# m4_Dev_Board.net
KiCad netlist of a schematic drawn in EAGLE
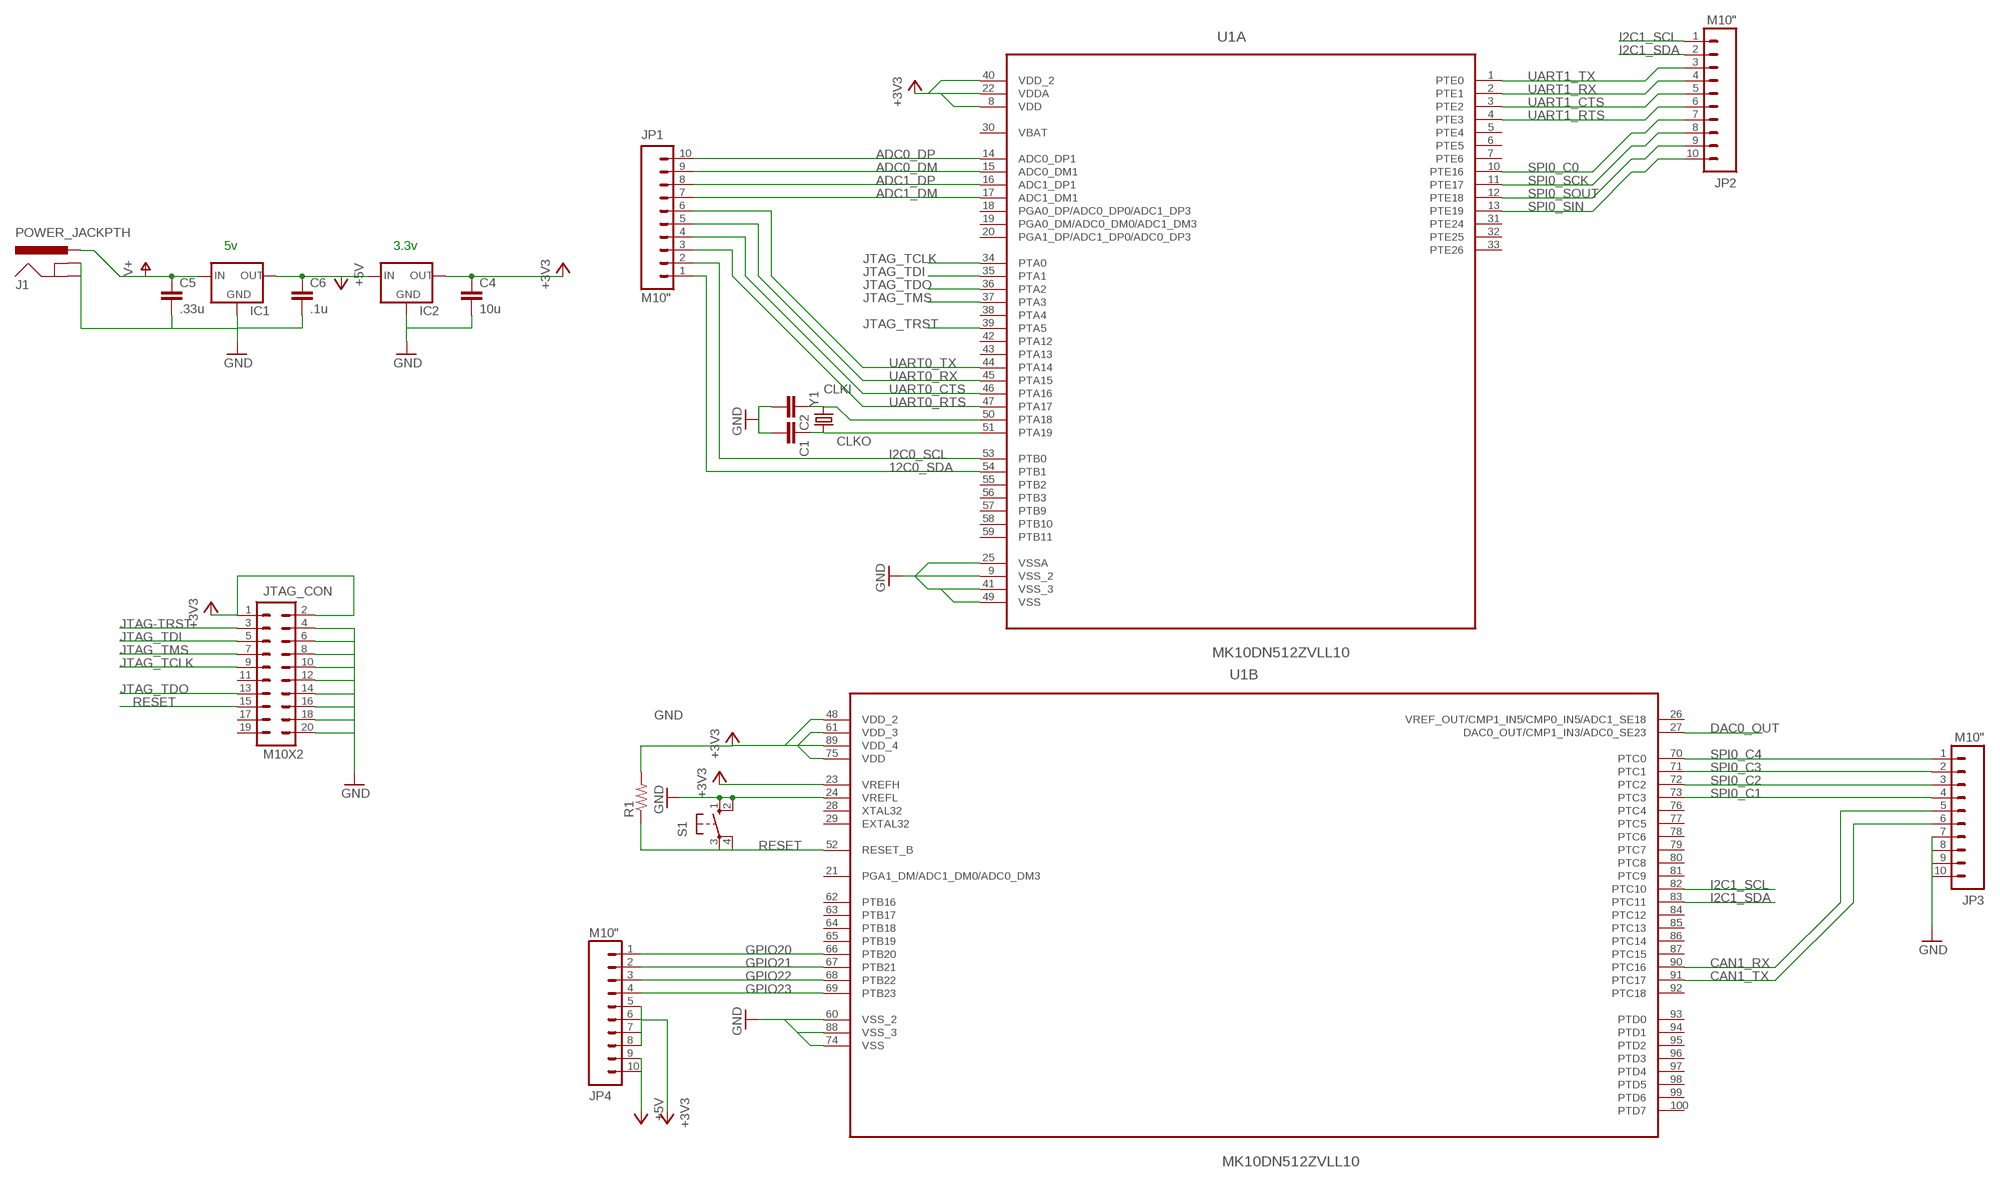
[diagram p0: schematic, sheet 1]

(export (version "E")
  (design (tool "Eeschema 10.0.6"))
  (components
    (comp (ref "C1")
      (value "CAPPTH1")
      (footprint "eagle-import:CAP-PTH-5MM")
      (libsource (lib "eagle-import") (part "CAPPTH1"))
    )
    (comp (ref "C2")
      (value "CAPPTH1")
      (footprint "eagle-import:CAP-PTH-5MM")
      (libsource (lib "eagle-import") (part "CAPPTH1"))
    )
    (comp (ref "C4")
      (value "10u")
      (footprint "eagle-import:CAP-PTH-5MM")
      (libsource (lib "eagle-import") (part "CAPPTH1"))
    )
    (comp (ref "C5")
      (value ".33u")
      (footprint "eagle-import:CAP-PTH-5MM")
      (libsource (lib "eagle-import") (part "CAPPTH1"))
    )
    (comp (ref "C6")
      (value ".1u")
      (footprint "eagle-import:CAP-PTH-5MM")
      (libsource (lib "eagle-import") (part "CAPPTH1"))
    )
    (comp (ref "IC1")
      (value "V_REG_78XXSINK")
      (footprint "eagle-import:TO220-IGO")
      (libsource (lib "eagle-import") (part "V_REG_78XXSINK"))
    )
    (comp (ref "IC2")
      (value "V_REG_78XXSINK")
      (footprint "eagle-import:TO220-IGO")
      (libsource (lib "eagle-import") (part "V_REG_78XXSINK"))
    )
    (comp (ref "J1")
      (value "POWER_JACKPTH")
      (footprint "eagle-import:POWER_JACK_PTH")
      (libsource (lib "eagle-import") (part "POWER_JACKPTH"))
    )
    (comp (ref "JP1")
      (value "M10\"")
      (footprint "eagle-import:1X10")
      (libsource (lib "eagle-import") (part "M10{dblquote}"))
    )
    (comp (ref "JP2")
      (value "M10\"")
      (footprint "eagle-import:1X10")
      (libsource (lib "eagle-import") (part "M10{dblquote}"))
    )
    (comp (ref "JP3")
      (value "M10\"")
      (footprint "eagle-import:1X10")
      (libsource (lib "eagle-import") (part "M10{dblquote}"))
    )
    (comp (ref "JP4")
      (value "M10\"")
      (footprint "eagle-import:1X10")
      (libsource (lib "eagle-import") (part "M10{dblquote}"))
    )
    (comp (ref "JTAG_CON")
      (value "M10X2")
      (footprint "eagle-import:2X10")
      (libsource (lib "eagle-import") (part "M10X2"))
    )
    (comp (ref "R1")
      (value "RESISTORPTH-1/4W")
      (footprint "eagle-import:AXIAL-0.4")
      (libsource (lib "eagle-import") (part "RESISTORPTH-1/4W"))
    )
    (comp (ref "S1")
      (value "10-XX")
      (footprint "eagle-import:B3F-10XX")
      (fields (field (name "MPN") "B3F-1000"))
      (libsource (lib "eagle-import") (part "10-XX"))
    )
    (comp (ref "U1")
      (value "MK10DN512ZVLL10")
      (footprint "eagle-import:QFP50P1600X1600X170-100N")
      (libsource (lib "eagle-import") (part "MK10DN512ZVLL10"))
    )
    (comp (ref "Y1")
      (value "CRYSTALHC49US")
      (footprint "eagle-import:HC49US")
      (libsource (lib "eagle-import") (part "CRYSTALHC49US"))
    )
  )
  (nets
    (net (code "1") (name "+3V3") (class "Default")
      (node (ref "C4") (pin "1") (pinfunction "1_1") (pintype "passive"))
      (node (ref "IC2") (pin "OUT") (pinfunction "OUT_OUT") (pintype "output"))
      (node (ref "JP4") (pin "5") (pinfunction "5_5") (pintype "passive"))
      (node (ref "JP4") (pin "6") (pinfunction "6_6") (pintype "passive"))
      (node (ref "JP4") (pin "7") (pinfunction "7_7") (pintype "passive"))
      (node (ref "JP4") (pin "8") (pinfunction "8_8") (pintype "passive"))
      (node (ref "JTAG_CON") (pin "1") (pinfunction "1_1") (pintype "passive"))
      (node (ref "JTAG_CON") (pin "2") (pinfunction "2_2") (pintype "passive"))
      (node (ref "R1") (pin "P$2") (pinfunction "2_P$2") (pintype "passive"))
      (node (ref "U1") (pin "22") (pinfunction "VDDA_22") (pintype "power_in"))
      (node (ref "U1") (pin "23") (pinfunction "VREFH_23") (pintype "passive"))
      (node (ref "U1") (pin "40") (pinfunction "VDD_2_40") (pintype "power_in"))
      (node (ref "U1") (pin "48") (pinfunction "VDD_2_48") (pintype "power_in"))
      (node (ref "U1") (pin "61") (pinfunction "VDD_3_61") (pintype "power_in"))
      (node (ref "U1") (pin "75") (pinfunction "VDD_75") (pintype "power_in"))
      (node (ref "U1") (pin "8") (pinfunction "VDD_8") (pintype "power_in"))
      (node (ref "U1") (pin "89") (pinfunction "VDD_4_89") (pintype "power_in"))
    )
    (net (code "2") (name "+5V") (class "Default")
      (node (ref "C6") (pin "1") (pinfunction "1_1") (pintype "passive"))
      (node (ref "IC1") (pin "OUT") (pinfunction "OUT_OUT") (pintype "output"))
      (node (ref "IC2") (pin "IN") (pinfunction "IN_IN") (pintype "input"))
      (node (ref "JP4") (pin "10") (pinfunction "10_10") (pintype "passive"))
      (node (ref "JP4") (pin "9") (pinfunction "9_9") (pintype "passive"))
    )
    (net (code "3") (name "/12C0_SDA") (class "Default")
      (node (ref "JP1") (pin "1") (pinfunction "1_1") (pintype "passive"))
      (node (ref "U1") (pin "54") (pinfunction "PTB1_54") (pintype "bidirectional"))
    )
    (net (code "4") (name "/ADC0_DM") (class "Default")
      (node (ref "JP1") (pin "9") (pinfunction "9_9") (pintype "passive"))
      (node (ref "U1") (pin "15") (pinfunction "ADC0_DM1_15") (pintype "passive"))
    )
    (net (code "5") (name "/ADC0_DP") (class "Default")
      (node (ref "JP1") (pin "10") (pinfunction "10_10") (pintype "passive"))
      (node (ref "U1") (pin "14") (pinfunction "ADC0_DP1_14") (pintype "passive"))
    )
    (net (code "6") (name "/ADC1_DM") (class "Default")
      (node (ref "JP1") (pin "7") (pinfunction "7_7") (pintype "passive"))
      (node (ref "U1") (pin "17") (pinfunction "ADC1_DM1_17") (pintype "passive"))
    )
    (net (code "7") (name "/ADC1_DP") (class "Default")
      (node (ref "JP1") (pin "8") (pinfunction "8_8") (pintype "passive"))
      (node (ref "U1") (pin "16") (pinfunction "ADC1_DP1_16") (pintype "passive"))
    )
    (net (code "8") (name "/CAN1_RX") (class "Default")
      (node (ref "JP3") (pin "5") (pinfunction "5_5") (pintype "passive"))
      (node (ref "U1") (pin "90") (pinfunction "PTC16_90") (pintype "bidirectional"))
    )
    (net (code "9") (name "/CAN1_TX") (class "Default")
      (node (ref "JP3") (pin "6") (pinfunction "6_6") (pintype "passive"))
      (node (ref "U1") (pin "91") (pinfunction "PTC17_91") (pintype "bidirectional"))
    )
    (net (code "10") (name "/CLKI") (class "Default")
      (node (ref "C2") (pin "1") (pinfunction "1_1") (pintype "passive"))
      (node (ref "U1") (pin "50") (pinfunction "PTA18_50") (pintype "bidirectional"))
      (node (ref "Y1") (pin "2") (pinfunction "2_2") (pintype "passive"))
    )
    (net (code "11") (name "/CLKO") (class "Default")
      (node (ref "C1") (pin "1") (pinfunction "1_1") (pintype "passive"))
      (node (ref "U1") (pin "51") (pinfunction "PTA19_51") (pintype "bidirectional"))
      (node (ref "Y1") (pin "1") (pinfunction "1_1") (pintype "passive"))
    )
    (net (code "12") (name "/DAC0_OUT") (class "Default")
      (node (ref "U1") (pin "27") (pinfunction "DAC0_OUT/CMP1_IN3/ADC0_SE23_27") (pintype "passive"))
    )
    (net (code "13") (name "/GPIO20") (class "Default")
      (node (ref "JP4") (pin "1") (pinfunction "1_1") (pintype "passive"))
      (node (ref "U1") (pin "66") (pinfunction "PTB20_66") (pintype "bidirectional"))
    )
    (net (code "14") (name "/GPIO21") (class "Default")
      (node (ref "JP4") (pin "2") (pinfunction "2_2") (pintype "passive"))
      (node (ref "U1") (pin "67") (pinfunction "PTB21_67") (pintype "bidirectional"))
    )
    (net (code "15") (name "/GPIO22") (class "Default")
      (node (ref "JP4") (pin "3") (pinfunction "3_3") (pintype "passive"))
      (node (ref "U1") (pin "68") (pinfunction "PTB22_68") (pintype "bidirectional"))
    )
    (net (code "16") (name "/GPIO23") (class "Default")
      (node (ref "JP4") (pin "4") (pinfunction "4_4") (pintype "passive"))
      (node (ref "U1") (pin "69") (pinfunction "PTB23_69") (pintype "bidirectional"))
    )
    (net (code "17") (name "/I2C0_SCL") (class "Default")
      (node (ref "JP1") (pin "2") (pinfunction "2_2") (pintype "passive"))
      (node (ref "U1") (pin "53") (pinfunction "PTB0_53") (pintype "bidirectional"))
    )
    (net (code "18") (name "/I2C1_SCL") (class "Default")
      (node (ref "JP2") (pin "1") (pinfunction "1_1") (pintype "passive"))
      (node (ref "U1") (pin "82") (pinfunction "PTC10_82") (pintype "bidirectional"))
    )
    (net (code "19") (name "/I2C1_SDA") (class "Default")
      (node (ref "JP2") (pin "2") (pinfunction "2_2") (pintype "passive"))
      (node (ref "U1") (pin "83") (pinfunction "PTC11_83") (pintype "bidirectional"))
    )
    (net (code "20") (name "/JTAG-TRST") (class "Default")
      (node (ref "JTAG_CON") (pin "3") (pinfunction "3_3") (pintype "passive"))
    )
    (net (code "21") (name "/JTAG_TCLK") (class "Default")
      (node (ref "JTAG_CON") (pin "9") (pinfunction "9_9") (pintype "passive"))
      (node (ref "U1") (pin "34") (pinfunction "PTA0_34") (pintype "bidirectional"))
    )
    (net (code "22") (name "/JTAG_TDI") (class "Default")
      (node (ref "JTAG_CON") (pin "5") (pinfunction "5_5") (pintype "passive"))
      (node (ref "U1") (pin "35") (pinfunction "PTA1_35") (pintype "bidirectional"))
    )
    (net (code "23") (name "/JTAG_TDO") (class "Default")
      (node (ref "JTAG_CON") (pin "13") (pinfunction "13_13") (pintype "passive"))
      (node (ref "U1") (pin "36") (pinfunction "PTA2_36") (pintype "bidirectional"))
    )
    (net (code "24") (name "/JTAG_TMS") (class "Default")
      (node (ref "JTAG_CON") (pin "7") (pinfunction "7_7") (pintype "passive"))
      (node (ref "U1") (pin "37") (pinfunction "PTA3_37") (pintype "bidirectional"))
    )
    (net (code "25") (name "/JTAG_TRST") (class "Default")
      (node (ref "U1") (pin "39") (pinfunction "PTA5_39") (pintype "bidirectional"))
    )
    (net (code "26") (name "/RESET") (class "Default")
      (node (ref "JTAG_CON") (pin "15") (pinfunction "15_15") (pintype "passive"))
      (node (ref "R1") (pin "P$1") (pinfunction "1_P$1") (pintype "passive"))
      (node (ref "S1") (pin "3") (pinfunction "P_3") (pintype "passive"))
      (node (ref "S1") (pin "4") (pinfunction "P1_4") (pintype "passive"))
      (node (ref "U1") (pin "52") (pinfunction "RESET_B_52") (pintype "passive"))
    )
    (net (code "27") (name "/SPI0_C0") (class "Default")
      (node (ref "JP2") (pin "7") (pinfunction "7_7") (pintype "passive"))
      (node (ref "U1") (pin "10") (pinfunction "PTE16_10") (pintype "bidirectional"))
    )
    (net (code "28") (name "/SPI0_C1") (class "Default")
      (node (ref "JP3") (pin "4") (pinfunction "4_4") (pintype "passive"))
      (node (ref "U1") (pin "73") (pinfunction "PTC3_73") (pintype "bidirectional"))
    )
    (net (code "29") (name "/SPI0_C2") (class "Default")
      (node (ref "JP3") (pin "3") (pinfunction "3_3") (pintype "passive"))
      (node (ref "U1") (pin "72") (pinfunction "PTC2_72") (pintype "bidirectional"))
    )
    (net (code "30") (name "/SPI0_C3") (class "Default")
      (node (ref "JP3") (pin "2") (pinfunction "2_2") (pintype "passive"))
      (node (ref "U1") (pin "71") (pinfunction "PTC1_71") (pintype "bidirectional"))
    )
    (net (code "31") (name "/SPI0_C4") (class "Default")
      (node (ref "JP3") (pin "1") (pinfunction "1_1") (pintype "passive"))
      (node (ref "U1") (pin "70") (pinfunction "PTC0_70") (pintype "bidirectional"))
    )
    (net (code "32") (name "/SPI0_SCK") (class "Default")
      (node (ref "JP2") (pin "8") (pinfunction "8_8") (pintype "passive"))
      (node (ref "U1") (pin "11") (pinfunction "PTE17_11") (pintype "bidirectional"))
    )
    (net (code "33") (name "/SPI0_SIN") (class "Default")
      (node (ref "JP2") (pin "10") (pinfunction "10_10") (pintype "passive"))
      (node (ref "U1") (pin "13") (pinfunction "PTE19_13") (pintype "bidirectional"))
    )
    (net (code "34") (name "/SPI0_SOUT") (class "Default")
      (node (ref "JP2") (pin "9") (pinfunction "9_9") (pintype "passive"))
      (node (ref "U1") (pin "12") (pinfunction "PTE18_12") (pintype "bidirectional"))
    )
    (net (code "35") (name "/UART0_CTS") (class "Default")
      (node (ref "JP1") (pin "4") (pinfunction "4_4") (pintype "passive"))
      (node (ref "U1") (pin "46") (pinfunction "PTA16_46") (pintype "bidirectional"))
    )
    (net (code "36") (name "/UART0_RTS") (class "Default")
      (node (ref "JP1") (pin "3") (pinfunction "3_3") (pintype "passive"))
      (node (ref "U1") (pin "47") (pinfunction "PTA17_47") (pintype "bidirectional"))
    )
    (net (code "37") (name "/UART0_RX") (class "Default")
      (node (ref "JP1") (pin "5") (pinfunction "5_5") (pintype "passive"))
      (node (ref "U1") (pin "45") (pinfunction "PTA15_45") (pintype "bidirectional"))
    )
    (net (code "38") (name "/UART0_TX") (class "Default")
      (node (ref "JP1") (pin "6") (pinfunction "6_6") (pintype "passive"))
      (node (ref "U1") (pin "44") (pinfunction "PTA14_44") (pintype "bidirectional"))
    )
    (net (code "39") (name "/UART1_CTS") (class "Default")
      (node (ref "JP2") (pin "5") (pinfunction "5_5") (pintype "passive"))
      (node (ref "U1") (pin "3") (pinfunction "PTE2_3") (pintype "bidirectional"))
    )
    (net (code "40") (name "/UART1_RTS") (class "Default")
      (node (ref "JP2") (pin "6") (pinfunction "6_6") (pintype "passive"))
      (node (ref "U1") (pin "4") (pinfunction "PTE3_4") (pintype "bidirectional"))
    )
    (net (code "41") (name "/UART1_RX") (class "Default")
      (node (ref "JP2") (pin "4") (pinfunction "4_4") (pintype "passive"))
      (node (ref "U1") (pin "2") (pinfunction "PTE1_2") (pintype "bidirectional"))
    )
    (net (code "42") (name "/UART1_TX") (class "Default")
      (node (ref "JP2") (pin "3") (pinfunction "3_3") (pintype "passive"))
      (node (ref "U1") (pin "1") (pinfunction "PTE0_1") (pintype "bidirectional"))
    )
    (net (code "43") (name "/VBAT") (class "Default")
      (node (ref "U1") (pin "30") (pinfunction "VBAT_30") (pintype "power_in"))
    )
    (net (code "44") (name "GND") (class "Default")
      (node (ref "C1") (pin "2") (pinfunction "2_2") (pintype "passive"))
      (node (ref "C2") (pin "2") (pinfunction "2_2") (pintype "passive"))
      (node (ref "C4") (pin "2") (pinfunction "2_2") (pintype "passive"))
      (node (ref "C5") (pin "2") (pinfunction "2_2") (pintype "passive"))
      (node (ref "C6") (pin "2") (pinfunction "2_2") (pintype "passive"))
      (node (ref "IC1") (pin "GND") (pinfunction "GND_GND") (pintype "input"))
      (node (ref "IC2") (pin "GND") (pinfunction "GND_GND") (pintype "input"))
      (node (ref "J1") (pin "GND") (pinfunction "GND_GND") (pintype "bidirectional"))
      (node (ref "J1") (pin "GNDBREAK") (pinfunction "GNDBREAK_GNDBREAK") (pintype "bidirectional"))
      (node (ref "JP3") (pin "10") (pinfunction "10_10") (pintype "passive"))
      (node (ref "JP3") (pin "7") (pinfunction "7_7") (pintype "passive"))
      (node (ref "JP3") (pin "8") (pinfunction "8_8") (pintype "passive"))
      (node (ref "JP3") (pin "9") (pinfunction "9_9") (pintype "passive"))
      (node (ref "JTAG_CON") (pin "10") (pinfunction "10_10") (pintype "passive"))
      (node (ref "JTAG_CON") (pin "12") (pinfunction "12_12") (pintype "passive"))
      (node (ref "JTAG_CON") (pin "14") (pinfunction "14_14") (pintype "passive"))
      (node (ref "JTAG_CON") (pin "16") (pinfunction "16_16") (pintype "passive"))
      (node (ref "JTAG_CON") (pin "18") (pinfunction "18_18") (pintype "passive"))
      (node (ref "JTAG_CON") (pin "20") (pinfunction "20_20") (pintype "passive"))
      (node (ref "JTAG_CON") (pin "4") (pinfunction "4_4") (pintype "passive"))
      (node (ref "JTAG_CON") (pin "6") (pinfunction "6_6") (pintype "passive"))
      (node (ref "JTAG_CON") (pin "8") (pinfunction "8_8") (pintype "passive"))
      (node (ref "S1") (pin "1") (pinfunction "S_1") (pintype "passive"))
      (node (ref "S1") (pin "2") (pinfunction "S1_2") (pintype "passive"))
      (node (ref "U1") (pin "24") (pinfunction "VREFL_24") (pintype "passive"))
      (node (ref "U1") (pin "25") (pinfunction "VSSA_25") (pintype "passive"))
      (node (ref "U1") (pin "41") (pinfunction "VSS_3_41") (pintype "passive"))
      (node (ref "U1") (pin "49") (pinfunction "VSS_49") (pintype "passive"))
      (node (ref "U1") (pin "60") (pinfunction "VSS_2_60") (pintype "passive"))
      (node (ref "U1") (pin "74") (pinfunction "VSS_74") (pintype "passive"))
      (node (ref "U1") (pin "88") (pinfunction "VSS_3_88") (pintype "passive"))
      (node (ref "U1") (pin "9") (pinfunction "VSS_2_9") (pintype "passive"))
    )
    (net (code "45") (name "V+") (class "Default")
      (node (ref "C5") (pin "1") (pinfunction "1_1") (pintype "passive"))
      (node (ref "IC1") (pin "IN") (pinfunction "IN_IN") (pintype "input"))
      (node (ref "J1") (pin "PWR") (pinfunction "PWR_PWR") (pintype "bidirectional"))
    )
    (net (code "46") (name "unconnected-(JTAG_CON-Pad11)") (class "Default")
      (node (ref "JTAG_CON") (pin "11") (pinfunction "11_11") (pintype "passive"))
    )
    (net (code "47") (name "unconnected-(JTAG_CON-Pad17)") (class "Default")
      (node (ref "JTAG_CON") (pin "17") (pinfunction "17_17") (pintype "passive"))
    )
    (net (code "48") (name "unconnected-(JTAG_CON-Pad19)") (class "Default")
      (node (ref "JTAG_CON") (pin "19") (pinfunction "19_19") (pintype "passive"))
    )
    (net (code "49") (name "unconnected-(U1A-PGA0_DM{slash}ADC0_DM0{slash}ADC1_DM3-Pad19)") (class "Default")
      (node (ref "U1") (pin "19") (pinfunction "PGA0_DM/ADC0_DM0/ADC1_DM3_19") (pintype "passive"))
    )
    (net (code "50") (name "unconnected-(U1A-PGA0_DP{slash}ADC0_DP0{slash}ADC1_DP3-Pad18)") (class "Default")
      (node (ref "U1") (pin "18") (pinfunction "PGA0_DP/ADC0_DP0/ADC1_DP3_18") (pintype "passive"))
    )
    (net (code "51") (name "unconnected-(U1A-PGA1_DP{slash}ADC1_DP0{slash}ADC0_DP3-Pad20)") (class "Default")
      (node (ref "U1") (pin "20") (pinfunction "PGA1_DP/ADC1_DP0/ADC0_DP3_20") (pintype "passive"))
    )
    (net (code "52") (name "unconnected-(U1A-PTA4-Pad38)") (class "Default")
      (node (ref "U1") (pin "38") (pinfunction "PTA4_38") (pintype "bidirectional"))
    )
    (net (code "53") (name "unconnected-(U1A-PTA12-Pad42)") (class "Default")
      (node (ref "U1") (pin "42") (pinfunction "PTA12_42") (pintype "bidirectional"))
    )
    (net (code "54") (name "unconnected-(U1A-PTA13-Pad43)") (class "Default")
      (node (ref "U1") (pin "43") (pinfunction "PTA13_43") (pintype "bidirectional"))
    )
    (net (code "55") (name "unconnected-(U1A-PTB2-Pad55)") (class "Default")
      (node (ref "U1") (pin "55") (pinfunction "PTB2_55") (pintype "bidirectional"))
    )
    (net (code "56") (name "unconnected-(U1A-PTB3-Pad56)") (class "Default")
      (node (ref "U1") (pin "56") (pinfunction "PTB3_56") (pintype "bidirectional"))
    )
    (net (code "57") (name "unconnected-(U1A-PTB9-Pad57)") (class "Default")
      (node (ref "U1") (pin "57") (pinfunction "PTB9_57") (pintype "bidirectional"))
    )
    (net (code "58") (name "unconnected-(U1A-PTB10-Pad58)") (class "Default")
      (node (ref "U1") (pin "58") (pinfunction "PTB10_58") (pintype "bidirectional"))
    )
    (net (code "59") (name "unconnected-(U1A-PTB11-Pad59)") (class "Default")
      (node (ref "U1") (pin "59") (pinfunction "PTB11_59") (pintype "bidirectional"))
    )
    (net (code "60") (name "unconnected-(U1A-PTE4-Pad5)") (class "Default")
      (node (ref "U1") (pin "5") (pinfunction "PTE4_5") (pintype "bidirectional"))
    )
    (net (code "61") (name "unconnected-(U1A-PTE5-Pad6)") (class "Default")
      (node (ref "U1") (pin "6") (pinfunction "PTE5_6") (pintype "bidirectional"))
    )
    (net (code "62") (name "unconnected-(U1A-PTE6-Pad7)") (class "Default")
      (node (ref "U1") (pin "7") (pinfunction "PTE6_7") (pintype "bidirectional"))
    )
    (net (code "63") (name "unconnected-(U1A-PTE24-Pad31)") (class "Default")
      (node (ref "U1") (pin "31") (pinfunction "PTE24_31") (pintype "bidirectional"))
    )
    (net (code "64") (name "unconnected-(U1A-PTE25-Pad32)") (class "Default")
      (node (ref "U1") (pin "32") (pinfunction "PTE25_32") (pintype "bidirectional"))
    )
    (net (code "65") (name "unconnected-(U1A-PTE26-Pad33)") (class "Default")
      (node (ref "U1") (pin "33") (pinfunction "PTE26_33") (pintype "bidirectional"))
    )
    (net (code "66") (name "unconnected-(U1B-EXTAL32-Pad29)") (class "Default")
      (node (ref "U1") (pin "29") (pinfunction "EXTAL32_29") (pintype "passive"))
    )
    (net (code "67") (name "unconnected-(U1B-PGA1_DM{slash}ADC1_DM0{slash}ADC0_DM3-Pad21)") (class "Default")
      (node (ref "U1") (pin "21") (pinfunction "PGA1_DM/ADC1_DM0/ADC0_DM3_21") (pintype "passive"))
    )
    (net (code "68") (name "unconnected-(U1B-PTB16-Pad62)") (class "Default")
      (node (ref "U1") (pin "62") (pinfunction "PTB16_62") (pintype "bidirectional"))
    )
    (net (code "69") (name "unconnected-(U1B-PTB17-Pad63)") (class "Default")
      (node (ref "U1") (pin "63") (pinfunction "PTB17_63") (pintype "bidirectional"))
    )
    (net (code "70") (name "unconnected-(U1B-PTB18-Pad64)") (class "Default")
      (node (ref "U1") (pin "64") (pinfunction "PTB18_64") (pintype "bidirectional"))
    )
    (net (code "71") (name "unconnected-(U1B-PTB19-Pad65)") (class "Default")
      (node (ref "U1") (pin "65") (pinfunction "PTB19_65") (pintype "bidirectional"))
    )
    (net (code "72") (name "unconnected-(U1B-PTC4-Pad76)") (class "Default")
      (node (ref "U1") (pin "76") (pinfunction "PTC4_76") (pintype "bidirectional"))
    )
    (net (code "73") (name "unconnected-(U1B-PTC5-Pad77)") (class "Default")
      (node (ref "U1") (pin "77") (pinfunction "PTC5_77") (pintype "bidirectional"))
    )
    (net (code "74") (name "unconnected-(U1B-PTC6-Pad78)") (class "Default")
      (node (ref "U1") (pin "78") (pinfunction "PTC6_78") (pintype "bidirectional"))
    )
    (net (code "75") (name "unconnected-(U1B-PTC7-Pad79)") (class "Default")
      (node (ref "U1") (pin "79") (pinfunction "PTC7_79") (pintype "bidirectional"))
    )
    (net (code "76") (name "unconnected-(U1B-PTC8-Pad80)") (class "Default")
      (node (ref "U1") (pin "80") (pinfunction "PTC8_80") (pintype "bidirectional"))
    )
    (net (code "77") (name "unconnected-(U1B-PTC9-Pad81)") (class "Default")
      (node (ref "U1") (pin "81") (pinfunction "PTC9_81") (pintype "bidirectional"))
    )
    (net (code "78") (name "unconnected-(U1B-PTC12-Pad84)") (class "Default")
      (node (ref "U1") (pin "84") (pinfunction "PTC12_84") (pintype "bidirectional"))
    )
    (net (code "79") (name "unconnected-(U1B-PTC13-Pad85)") (class "Default")
      (node (ref "U1") (pin "85") (pinfunction "PTC13_85") (pintype "bidirectional"))
    )
    (net (code "80") (name "unconnected-(U1B-PTC14-Pad86)") (class "Default")
      (node (ref "U1") (pin "86") (pinfunction "PTC14_86") (pintype "bidirectional"))
    )
    (net (code "81") (name "unconnected-(U1B-PTC15-Pad87)") (class "Default")
      (node (ref "U1") (pin "87") (pinfunction "PTC15_87") (pintype "bidirectional"))
    )
    (net (code "82") (name "unconnected-(U1B-PTC18-Pad92)") (class "Default")
      (node (ref "U1") (pin "92") (pinfunction "PTC18_92") (pintype "bidirectional"))
    )
    (net (code "83") (name "unconnected-(U1B-PTD0-Pad93)") (class "Default")
      (node (ref "U1") (pin "93") (pinfunction "PTD0_93") (pintype "bidirectional"))
    )
    (net (code "84") (name "unconnected-(U1B-PTD1-Pad94)") (class "Default")
      (node (ref "U1") (pin "94") (pinfunction "PTD1_94") (pintype "bidirectional"))
    )
    (net (code "85") (name "unconnected-(U1B-PTD2-Pad95)") (class "Default")
      (node (ref "U1") (pin "95") (pinfunction "PTD2_95") (pintype "bidirectional"))
    )
    (net (code "86") (name "unconnected-(U1B-PTD3-Pad96)") (class "Default")
      (node (ref "U1") (pin "96") (pinfunction "PTD3_96") (pintype "bidirectional"))
    )
    (net (code "87") (name "unconnected-(U1B-PTD4-Pad97)") (class "Default")
      (node (ref "U1") (pin "97") (pinfunction "PTD4_97") (pintype "bidirectional"))
    )
    (net (code "88") (name "unconnected-(U1B-PTD5-Pad98)") (class "Default")
      (node (ref "U1") (pin "98") (pinfunction "PTD5_98") (pintype "bidirectional"))
    )
    (net (code "89") (name "unconnected-(U1B-PTD6-Pad99)") (class "Default")
      (node (ref "U1") (pin "99") (pinfunction "PTD6_99") (pintype "bidirectional"))
    )
    (net (code "90") (name "unconnected-(U1B-PTD7-Pad100)") (class "Default")
      (node (ref "U1") (pin "100") (pinfunction "PTD7_100") (pintype "bidirectional"))
    )
    (net (code "91") (name "unconnected-(U1B-VREF_OUT{slash}CMP1_IN5{slash}CMP0_IN5{slash}ADC1_SE18-Pad26)") (class "Default")
      (node (ref "U1") (pin "26") (pinfunction "VREF_OUT/CMP1_IN5/CMP0_IN5/ADC1_SE18_26") (pintype "passive"))
    )
    (net (code "92") (name "unconnected-(U1B-XTAL32-Pad28)") (class "Default")
      (node (ref "U1") (pin "28") (pinfunction "XTAL32_28") (pintype "passive"))
    )
  )
)
